# precharger_rev1.net
KiCad netlist of a schematic drawn in EAGLE
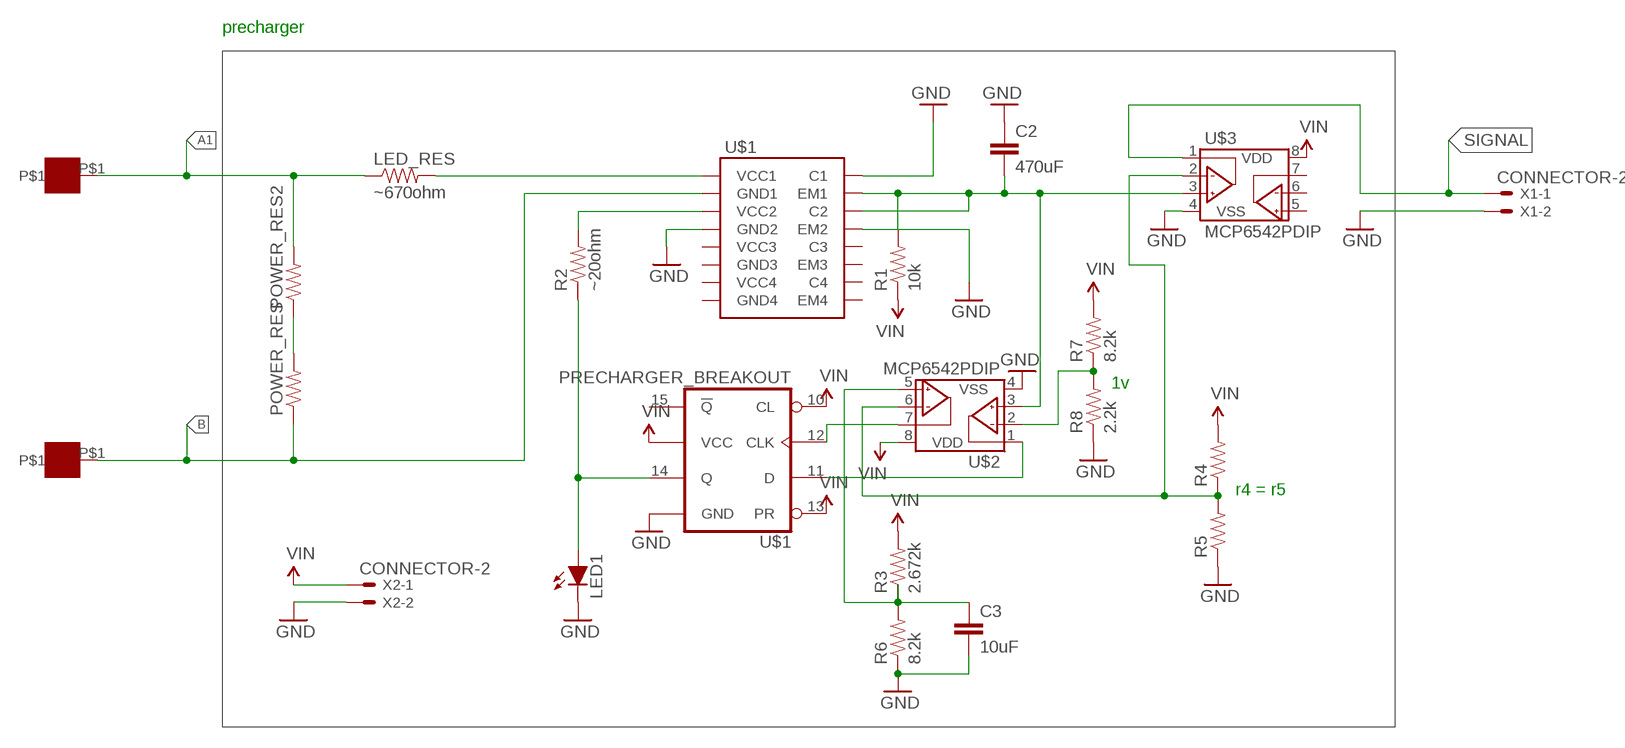
[diagram p0: schematic, sheet 1]

(export (version "E")
  (design (tool "Eeschema 10.0.6"))
  (components
    (comp (ref "+")
      (value "SOLDER_PAD")
      (footprint "eagle-import:SOLDER_PAD_XSMALL")
      (libsource (lib "eagle-import") (part "SOLDER_PAD"))
    )
    (comp (ref "-")
      (value "SOLDER_PAD")
      (footprint "eagle-import:SOLDER_PAD_XSMALL")
      (libsource (lib "eagle-import") (part "SOLDER_PAD"))
    )
    (comp (ref "C2")
      (value "470uF")
      (footprint "eagle-import:CAP-PTH-5MM")
      (libsource (lib "eagle-import") (part "CAPPTH1"))
    )
    (comp (ref "C3")
      (value "10uF")
      (footprint "eagle-import:CAP-PTH-5MM")
      (libsource (lib "eagle-import") (part "CAPPTH1"))
    )
    (comp (ref "LED1")
      (value "LED-3MM")
      (footprint "eagle-import:LED-3MM")
      (libsource (lib "eagle-import") (part "LED-3MM"))
    )
    (comp (ref "LED_RES")
      (value "~670ohm")
      (footprint "eagle-import:AXIAL-0.3")
      (libsource (lib "eagle-import") (part "RESISTORAXIAL-0.3"))
    )
    (comp (ref "POWER_RES")
      (value "RESISTOR10W")
      (footprint "eagle-import:10W_RESISTOR_VISHAY")
      (libsource (lib "eagle-import") (part "RESISTOR10W"))
    )
    (comp (ref "POWER_RES2")
      (value "RESISTOR10W")
      (footprint "eagle-import:10W_RESISTOR_VISHAY")
      (libsource (lib "eagle-import") (part "RESISTOR10W"))
    )
    (comp (ref "R1")
      (value "10k")
      (footprint "eagle-import:AXIAL-0.3")
      (libsource (lib "eagle-import") (part "RESISTORAXIAL-0.3"))
    )
    (comp (ref "R2")
      (value "~20ohm")
      (footprint "eagle-import:AXIAL-0.3")
      (libsource (lib "eagle-import") (part "RESISTORAXIAL-0.3"))
    )
    (comp (ref "R3")
      (value "2.672k")
      (footprint "eagle-import:AXIAL-0.3")
      (libsource (lib "eagle-import") (part "RESISTORAXIAL-0.3"))
    )
    (comp (ref "R4")
      (value "RESISTORAXIAL-0.3")
      (footprint "eagle-import:AXIAL-0.3")
      (libsource (lib "eagle-import") (part "RESISTORAXIAL-0.3"))
    )
    (comp (ref "R5")
      (value "RESISTORAXIAL-0.3")
      (footprint "eagle-import:AXIAL-0.3")
      (libsource (lib "eagle-import") (part "RESISTORAXIAL-0.3"))
    )
    (comp (ref "R6")
      (value "8.2k")
      (footprint "eagle-import:AXIAL-0.3")
      (libsource (lib "eagle-import") (part "RESISTORAXIAL-0.3"))
    )
    (comp (ref "R7")
      (value "8.2k")
      (footprint "eagle-import:AXIAL-0.3")
      (libsource (lib "eagle-import") (part "RESISTORAXIAL-0.3"))
    )
    (comp (ref "R8")
      (value "2.2k")
      (footprint "eagle-import:AXIAL-0.3")
      (libsource (lib "eagle-import") (part "RESISTORAXIAL-0.3"))
    )
    (comp (ref "U$1")
      (value "PRECHARGER_BREAKOUT")
      (footprint "eagle-import:PRECHARGER_BREAKOUT")
      (libsource (lib "eagle-import") (part "PRECHARGER_BREAKOUT"))
    )
    (comp (ref "U$2")
      (value "MCP6542PDIP")
      (footprint "eagle-import:DIL08")
      (libsource (lib "eagle-import") (part "MCP6542PDIP"))
    )
    (comp (ref "U$3")
      (value "MCP6542PDIP")
      (footprint "eagle-import:DIL08")
      (libsource (lib "eagle-import") (part "MCP6542PDIP"))
    )
    (comp (ref "X1")
      (value "CONNECTOR-2")
      (footprint "eagle-import:MINIFIT_5566-2")
      (libsource (lib "eagle-import") (part "CONNECTOR-2"))
    )
    (comp (ref "X2")
      (value "CONNECTOR-2")
      (footprint "eagle-import:MINIFIT_5566-2")
      (libsource (lib "eagle-import") (part "CONNECTOR-2"))
    )
  )
  (nets
    (net (code "1") (name "A1") (class "Default")
      (node (ref "+") (pin "P$1") (pinfunction "P$1_P$1") (pintype "bidirectional"))
      (node (ref "LED_RES") (pin "P$1") (pinfunction "1_P$1") (pintype "passive"))
      (node (ref "POWER_RES2") (pin "2") (pinfunction "2_2") (pintype "passive"))
    )
    (net (code "2") (name "B") (class "Default")
      (node (ref "-") (pin "P$1") (pinfunction "P$1_P$1") (pintype "bidirectional"))
      (node (ref "POWER_RES") (pin "1") (pinfunction "1_1") (pintype "passive"))
      (node (ref "U$1") (pin "2") (pinfunction "GND1_2") (pintype "passive"))
    )
    (net (code "3") (name "GND") (class "Default")
      (node (ref "C2") (pin "1") (pinfunction "1_1") (pintype "passive"))
      (node (ref "C3") (pin "2") (pinfunction "2_2") (pintype "passive"))
      (node (ref "LED1") (pin "K") (pinfunction "C_K") (pintype "passive"))
      (node (ref "R5") (pin "P$1") (pinfunction "1_P$1") (pintype "passive"))
      (node (ref "R6") (pin "P$1") (pinfunction "1_P$1") (pintype "passive"))
      (node (ref "R8") (pin "P$1") (pinfunction "1_P$1") (pintype "passive"))
      (node (ref "U$1") (pin "16") (pinfunction "GND_16") (pintype "bidirectional"))
      (node (ref "U$1") (pin "29") (pinfunction "EM2_29") (pintype "passive"))
      (node (ref "U$1") (pin "32") (pinfunction "C1_32") (pintype "passive"))
      (node (ref "U$1") (pin "4") (pinfunction "GND2_4") (pintype "passive"))
      (node (ref "U$2") (pin "4") (pinfunction "VSS_4") (pintype "passive"))
      (node (ref "U$3") (pin "4") (pinfunction "VSS_4") (pintype "passive"))
      (node (ref "X1") (pin "2") (pinfunction "S_2") (pintype "passive"))
      (node (ref "X2") (pin "2") (pinfunction "S_2") (pintype "passive"))
    )
    (net (code "4") (name "Net-(LED_RES-2)") (class "Default")
      (node (ref "LED_RES") (pin "P$2") (pinfunction "2_P$2") (pintype "passive"))
      (node (ref "U$1") (pin "1") (pinfunction "VCC1_1") (pintype "passive"))
    )
    (net (code "5") (name "Net-(POWER_RES-Pad2)") (class "Default")
      (node (ref "POWER_RES") (pin "2") (pinfunction "2_2") (pintype "passive"))
      (node (ref "POWER_RES2") (pin "1") (pinfunction "1_1") (pintype "passive"))
    )
    (net (code "6") (name "Net-(R1-2)") (class "Default")
      (node (ref "C2") (pin "2") (pinfunction "2_2") (pintype "passive"))
      (node (ref "R1") (pin "P$2") (pinfunction "2_P$2") (pintype "passive"))
      (node (ref "U$1") (pin "30") (pinfunction "C2_30") (pintype "passive"))
      (node (ref "U$1") (pin "31") (pinfunction "EM1_31") (pintype "passive"))
      (node (ref "U$2") (pin "3") (pinfunction "VINA+_3") (pintype "passive"))
      (node (ref "U$3") (pin "3") (pinfunction "VINA+_3") (pintype "passive"))
    )
    (net (code "7") (name "Net-(R2-1)") (class "Default")
      (node (ref "LED1") (pin "A") (pinfunction "A_A") (pintype "passive"))
      (node (ref "R2") (pin "P$1") (pinfunction "1_P$1") (pintype "passive"))
      (node (ref "U$1") (pin "14") (pinfunction "Q_14") (pintype "output"))
    )
    (net (code "8") (name "Net-(R2-2)") (class "Default")
      (node (ref "R2") (pin "P$2") (pinfunction "2_P$2") (pintype "passive"))
      (node (ref "U$1") (pin "3") (pinfunction "VCC2_3") (pintype "passive"))
    )
    (net (code "9") (name "Net-(R3-1)") (class "Default")
      (node (ref "C3") (pin "1") (pinfunction "1_1") (pintype "passive"))
      (node (ref "R3") (pin "P$1") (pinfunction "1_P$1") (pintype "passive"))
      (node (ref "R6") (pin "P$2") (pinfunction "2_P$2") (pintype "passive"))
      (node (ref "U$2") (pin "5") (pinfunction "VINB+_5") (pintype "passive"))
    )
    (net (code "10") (name "Net-(R4-1)") (class "Default")
      (node (ref "R4") (pin "P$1") (pinfunction "1_P$1") (pintype "passive"))
      (node (ref "R5") (pin "P$2") (pinfunction "2_P$2") (pintype "passive"))
      (node (ref "U$2") (pin "6") (pinfunction "VINB-_6") (pintype "passive"))
      (node (ref "U$3") (pin "2") (pinfunction "VINA-_2") (pintype "passive"))
    )
    (net (code "11") (name "Net-(R7-1)") (class "Default")
      (node (ref "R7") (pin "P$1") (pinfunction "1_P$1") (pintype "passive"))
      (node (ref "R8") (pin "P$2") (pinfunction "2_P$2") (pintype "passive"))
      (node (ref "U$2") (pin "2") (pinfunction "VINA-_2") (pintype "passive"))
    )
    (net (code "12") (name "Net-(U$1-CLK)") (class "Default")
      (node (ref "U$1") (pin "12") (pinfunction "CLK_12") (pintype "input"))
      (node (ref "U$2") (pin "7") (pinfunction "VOUTB_7") (pintype "passive"))
    )
    (net (code "13") (name "Net-(U$1-D)") (class "Default")
      (node (ref "U$1") (pin "11") (pinfunction "D_11") (pintype "input"))
      (node (ref "U$2") (pin "1") (pinfunction "VOUTA_1") (pintype "passive"))
    )
    (net (code "14") (name "SIGNAL") (class "Default")
      (node (ref "U$3") (pin "1") (pinfunction "VOUTA_1") (pintype "passive"))
      (node (ref "X1") (pin "1") (pinfunction "S_1") (pintype "passive"))
    )
    (net (code "15") (name "VIN") (class "Default")
      (node (ref "R1") (pin "P$1") (pinfunction "1_P$1") (pintype "passive"))
      (node (ref "R3") (pin "P$2") (pinfunction "2_P$2") (pintype "passive"))
      (node (ref "R4") (pin "P$2") (pinfunction "2_P$2") (pintype "passive"))
      (node (ref "R7") (pin "P$2") (pinfunction "2_P$2") (pintype "passive"))
      (node (ref "U$1") (pin "10") (pinfunction "CL_10") (pintype "input"))
      (node (ref "U$1") (pin "13") (pinfunction "PR_13") (pintype "input"))
      (node (ref "U$1") (pin "23") (pinfunction "VCC_23") (pintype "bidirectional"))
      (node (ref "U$2") (pin "8") (pinfunction "VDD_8") (pintype "passive"))
      (node (ref "U$3") (pin "8") (pinfunction "VDD_8") (pintype "passive"))
      (node (ref "X2") (pin "1") (pinfunction "S_1") (pintype "passive"))
    )
    (net (code "16") (name "unconnected-(U$1-C3-Pad28)") (class "Default")
      (node (ref "U$1") (pin "28") (pinfunction "C3_28") (pintype "passive"))
    )
    (net (code "17") (name "unconnected-(U$1-C4-Pad26)") (class "Default")
      (node (ref "U$1") (pin "26") (pinfunction "C4_26") (pintype "passive"))
    )
    (net (code "18") (name "unconnected-(U$1-EM3-Pad27)") (class "Default")
      (node (ref "U$1") (pin "27") (pinfunction "EM3_27") (pintype "passive"))
    )
    (net (code "19") (name "unconnected-(U$1-EM4-Pad25)") (class "Default")
      (node (ref "U$1") (pin "25") (pinfunction "EM4_25") (pintype "passive"))
    )
    (net (code "20") (name "unconnected-(U$1-GND3-Pad6)") (class "Default")
      (node (ref "U$1") (pin "6") (pinfunction "GND3_6") (pintype "passive"))
    )
    (net (code "21") (name "unconnected-(U$1-GND4-Pad8)") (class "Default")
      (node (ref "U$1") (pin "8") (pinfunction "GND4_8") (pintype "passive"))
    )
    (net (code "22") (name "unconnected-(U$1-VCC3-Pad5)") (class "Default")
      (node (ref "U$1") (pin "5") (pinfunction "VCC3_5") (pintype "passive"))
    )
    (net (code "23") (name "unconnected-(U$1-VCC4-Pad7)") (class "Default")
      (node (ref "U$1") (pin "7") (pinfunction "VCC4_7") (pintype "passive"))
    )
    (net (code "24") (name "unconnected-(U$1-~{Q}-Pad15)") (class "Default")
      (node (ref "U$1") (pin "15") (pinfunction "~{Q}_15") (pintype "output"))
    )
    (net (code "25") (name "unconnected-(U$3-VINB+-Pad5)") (class "Default")
      (node (ref "U$3") (pin "5") (pinfunction "VINB+_5") (pintype "passive"))
    )
    (net (code "26") (name "unconnected-(U$3-VINB--Pad6)") (class "Default")
      (node (ref "U$3") (pin "6") (pinfunction "VINB-_6") (pintype "passive"))
    )
    (net (code "27") (name "unconnected-(U$3-VOUTB-Pad7)") (class "Default")
      (node (ref "U$3") (pin "7") (pinfunction "VOUTB_7") (pintype "passive"))
    )
  )
)
